# ECG_BLE_radio.net
KiCad netlist of a schematic drawn in Altium Designer
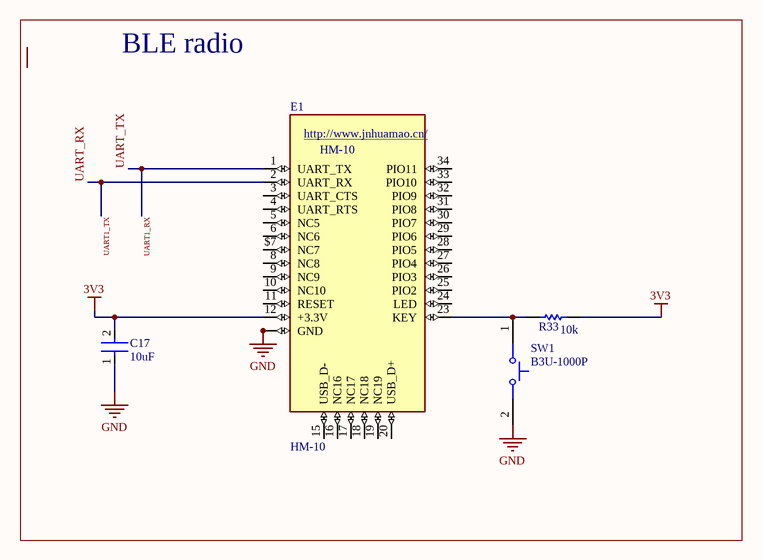
[diagram p0: ECG_BLE_radio.SchDoc]

(export (version "E")
  (design (tool "Eeschema 10.0.6"))
  (components
    (comp (ref "C17")
      (value "10uF")
      (footprint "CAP-0805-IPC_B")
      (description "50V 10uF X5R 卤10% 0805 Multilayer Ceramic Capacitors MLCC - SMD/SMT ROHS")
      (fields
        (field (name "MANUFACTURER") "Samsung Electro-Mechanics")
        (field (name "MANUFACTURER PART NUMBER") "CL21A106KBYQNNE")
      )
      (libsource (lib "ecg_device_components") (part "10uF CAP 0805 10V"))
    )
    (comp (ref "E1")
      (value "HM-10")
      (footprint "HM-10")
      (description "Bluetooth 4.0 module with 4pin base board that can support iphone4s or later.")
      (fields (field (name "MF") "Jinan Huamao Technology"))
      (libsource (lib "ecg_device_components") (part "HM-10"))
    )
    (comp (ref "R33")
      (value "10k")
      (footprint "RES-0603-IPC_B")
      (fields (field (name "TOLERANCE") "0.5%"))
      (libsource (lib "ecg_device_components") (part "1k RES-0603-IPC-B_1"))
    )
    (comp (ref "SW1")
      (value "B3U-1000P")
      (footprint "OMRON-B3U-1000_V")
      (description "Tactile Switch, SPST-NO, 0.05 A, 12 V, -25 to 70 degC, 2-Pin SMD, RoHS, Tape and Reel")
      (fields (field (name "MANUFACTURER") "Omron Electronic Components"))
      (libsource (lib "ecg_device_components") (part "Tactile Switch"))
    )
  )
  (nets
    (net (code "1") (name "/UART1_RX") (class "Default")
      (node (ref "E1") (pin "1") (pinfunction "UART_TX_1") (pintype "bidirectional"))
    )
    (net (code "2") (name "/UART1_TX") (class "Default")
      (node (ref "E1") (pin "2") (pinfunction "UART_RX_2") (pintype "bidirectional"))
    )
    (net (code "3") (name "3V3") (class "Default")
      (node (ref "C17") (pin "2") (pinfunction "2_2") (pintype "passive"))
      (node (ref "E1") (pin "12") (pinfunction "+3.3V_12") (pintype "bidirectional"))
      (node (ref "R33") (pin "2") (pinfunction "2_2") (pintype "passive"))
    )
    (net (code "4") (name "GND") (class "Default")
      (node (ref "C17") (pin "1") (pinfunction "1_1") (pintype "passive"))
      (node (ref "E1") (pin "13") (pinfunction "GND_13") (pintype "bidirectional"))
      (node (ref "E1") (pin "14") (pinfunction "GND_14") (pintype "bidirectional"))
      (node (ref "E1") (pin "21") (pinfunction "GND_21") (pintype "bidirectional"))
      (node (ref "E1") (pin "22") (pinfunction "GND_22") (pintype "bidirectional"))
      (node (ref "SW1") (pin "2") (pinfunction "2_2") (pintype "passive"))
    )
    (net (code "5") (name "Net-(E1-KEY)") (class "Default")
      (node (ref "E1") (pin "23") (pinfunction "KEY_23") (pintype "bidirectional"))
      (node (ref "R33") (pin "1") (pinfunction "1_1") (pintype "passive"))
      (node (ref "SW1") (pin "1") (pinfunction "1_1") (pintype "passive"))
    )
    (net (code "6") (name "unconnected-(E1-LED-Pad24)") (class "Default")
      (node (ref "E1") (pin "24") (pinfunction "LED_24") (pintype "bidirectional"))
    )
    (net (code "7") (name "unconnected-(E1-NC5-Pad5)") (class "Default")
      (node (ref "E1") (pin "5") (pinfunction "NC5_5") (pintype "bidirectional"))
    )
    (net (code "8") (name "unconnected-(E1-NC6-Pad6)") (class "Default")
      (node (ref "E1") (pin "6") (pinfunction "NC6_6") (pintype "bidirectional"))
    )
    (net (code "9") (name "unconnected-(E1-NC7-Pad$7)") (class "Default")
      (node (ref "E1") (pin "$7") (pinfunction "NC7_$7") (pintype "bidirectional"))
    )
    (net (code "10") (name "unconnected-(E1-NC8-Pad8)") (class "Default")
      (node (ref "E1") (pin "8") (pinfunction "NC8_8") (pintype "bidirectional"))
    )
    (net (code "11") (name "unconnected-(E1-NC9-Pad9)") (class "Default")
      (node (ref "E1") (pin "9") (pinfunction "NC9_9") (pintype "bidirectional"))
    )
    (net (code "12") (name "unconnected-(E1-NC10-Pad10)") (class "Default")
      (node (ref "E1") (pin "10") (pinfunction "NC10_10") (pintype "bidirectional"))
    )
    (net (code "13") (name "unconnected-(E1-NC16-Pad16)") (class "Default")
      (node (ref "E1") (pin "16") (pinfunction "NC16_16") (pintype "bidirectional"))
    )
    (net (code "14") (name "unconnected-(E1-NC17-Pad17)") (class "Default")
      (node (ref "E1") (pin "17") (pinfunction "NC17_17") (pintype "bidirectional"))
    )
    (net (code "15") (name "unconnected-(E1-NC18-Pad18)") (class "Default")
      (node (ref "E1") (pin "18") (pinfunction "NC18_18") (pintype "bidirectional"))
    )
    (net (code "16") (name "unconnected-(E1-NC19-Pad19)") (class "Default")
      (node (ref "E1") (pin "19") (pinfunction "NC19_19") (pintype "bidirectional"))
    )
    (net (code "17") (name "unconnected-(E1-PIO2-Pad25)") (class "Default")
      (node (ref "E1") (pin "25") (pinfunction "PIO2_25") (pintype "bidirectional"))
    )
    (net (code "18") (name "unconnected-(E1-PIO3-Pad26)") (class "Default")
      (node (ref "E1") (pin "26") (pinfunction "PIO3_26") (pintype "bidirectional"))
    )
    (net (code "19") (name "unconnected-(E1-PIO4-Pad27)") (class "Default")
      (node (ref "E1") (pin "27") (pinfunction "PIO4_27") (pintype "bidirectional"))
    )
    (net (code "20") (name "unconnected-(E1-PIO5-Pad28)") (class "Default")
      (node (ref "E1") (pin "28") (pinfunction "PIO5_28") (pintype "bidirectional"))
    )
    (net (code "21") (name "unconnected-(E1-PIO6-Pad29)") (class "Default")
      (node (ref "E1") (pin "29") (pinfunction "PIO6_29") (pintype "bidirectional"))
    )
    (net (code "22") (name "unconnected-(E1-PIO7-Pad30)") (class "Default")
      (node (ref "E1") (pin "30") (pinfunction "PIO7_30") (pintype "bidirectional"))
    )
    (net (code "23") (name "unconnected-(E1-PIO8-Pad31)") (class "Default")
      (node (ref "E1") (pin "31") (pinfunction "PIO8_31") (pintype "bidirectional"))
    )
    (net (code "24") (name "unconnected-(E1-PIO9-Pad32)") (class "Default")
      (node (ref "E1") (pin "32") (pinfunction "PIO9_32") (pintype "bidirectional"))
    )
    (net (code "25") (name "unconnected-(E1-PIO10-Pad33)") (class "Default")
      (node (ref "E1") (pin "33") (pinfunction "PIO10_33") (pintype "bidirectional"))
    )
    (net (code "26") (name "unconnected-(E1-PIO11-Pad34)") (class "Default")
      (node (ref "E1") (pin "34") (pinfunction "PIO11_34") (pintype "bidirectional"))
    )
    (net (code "27") (name "unconnected-(E1-RESET-Pad11)") (class "Default")
      (node (ref "E1") (pin "11") (pinfunction "RESET_11") (pintype "bidirectional"))
    )
    (net (code "28") (name "unconnected-(E1-UART_CTS-Pad3)") (class "Default")
      (node (ref "E1") (pin "3") (pinfunction "UART_CTS_3") (pintype "bidirectional"))
    )
    (net (code "29") (name "unconnected-(E1-UART_RTS-Pad4)") (class "Default")
      (node (ref "E1") (pin "4") (pinfunction "UART_RTS_4") (pintype "bidirectional"))
    )
    (net (code "30") (name "unconnected-(E1-USB_D+-Pad20)") (class "Default")
      (node (ref "E1") (pin "20") (pinfunction "USB_D+_20") (pintype "bidirectional"))
    )
    (net (code "31") (name "unconnected-(E1-USB_D--Pad15)") (class "Default")
      (node (ref "E1") (pin "15") (pinfunction "USB_D-_15") (pintype "bidirectional"))
    )
  )
)
